# SAOT.net
KiCad netlist of a schematic drawn in EAGLE
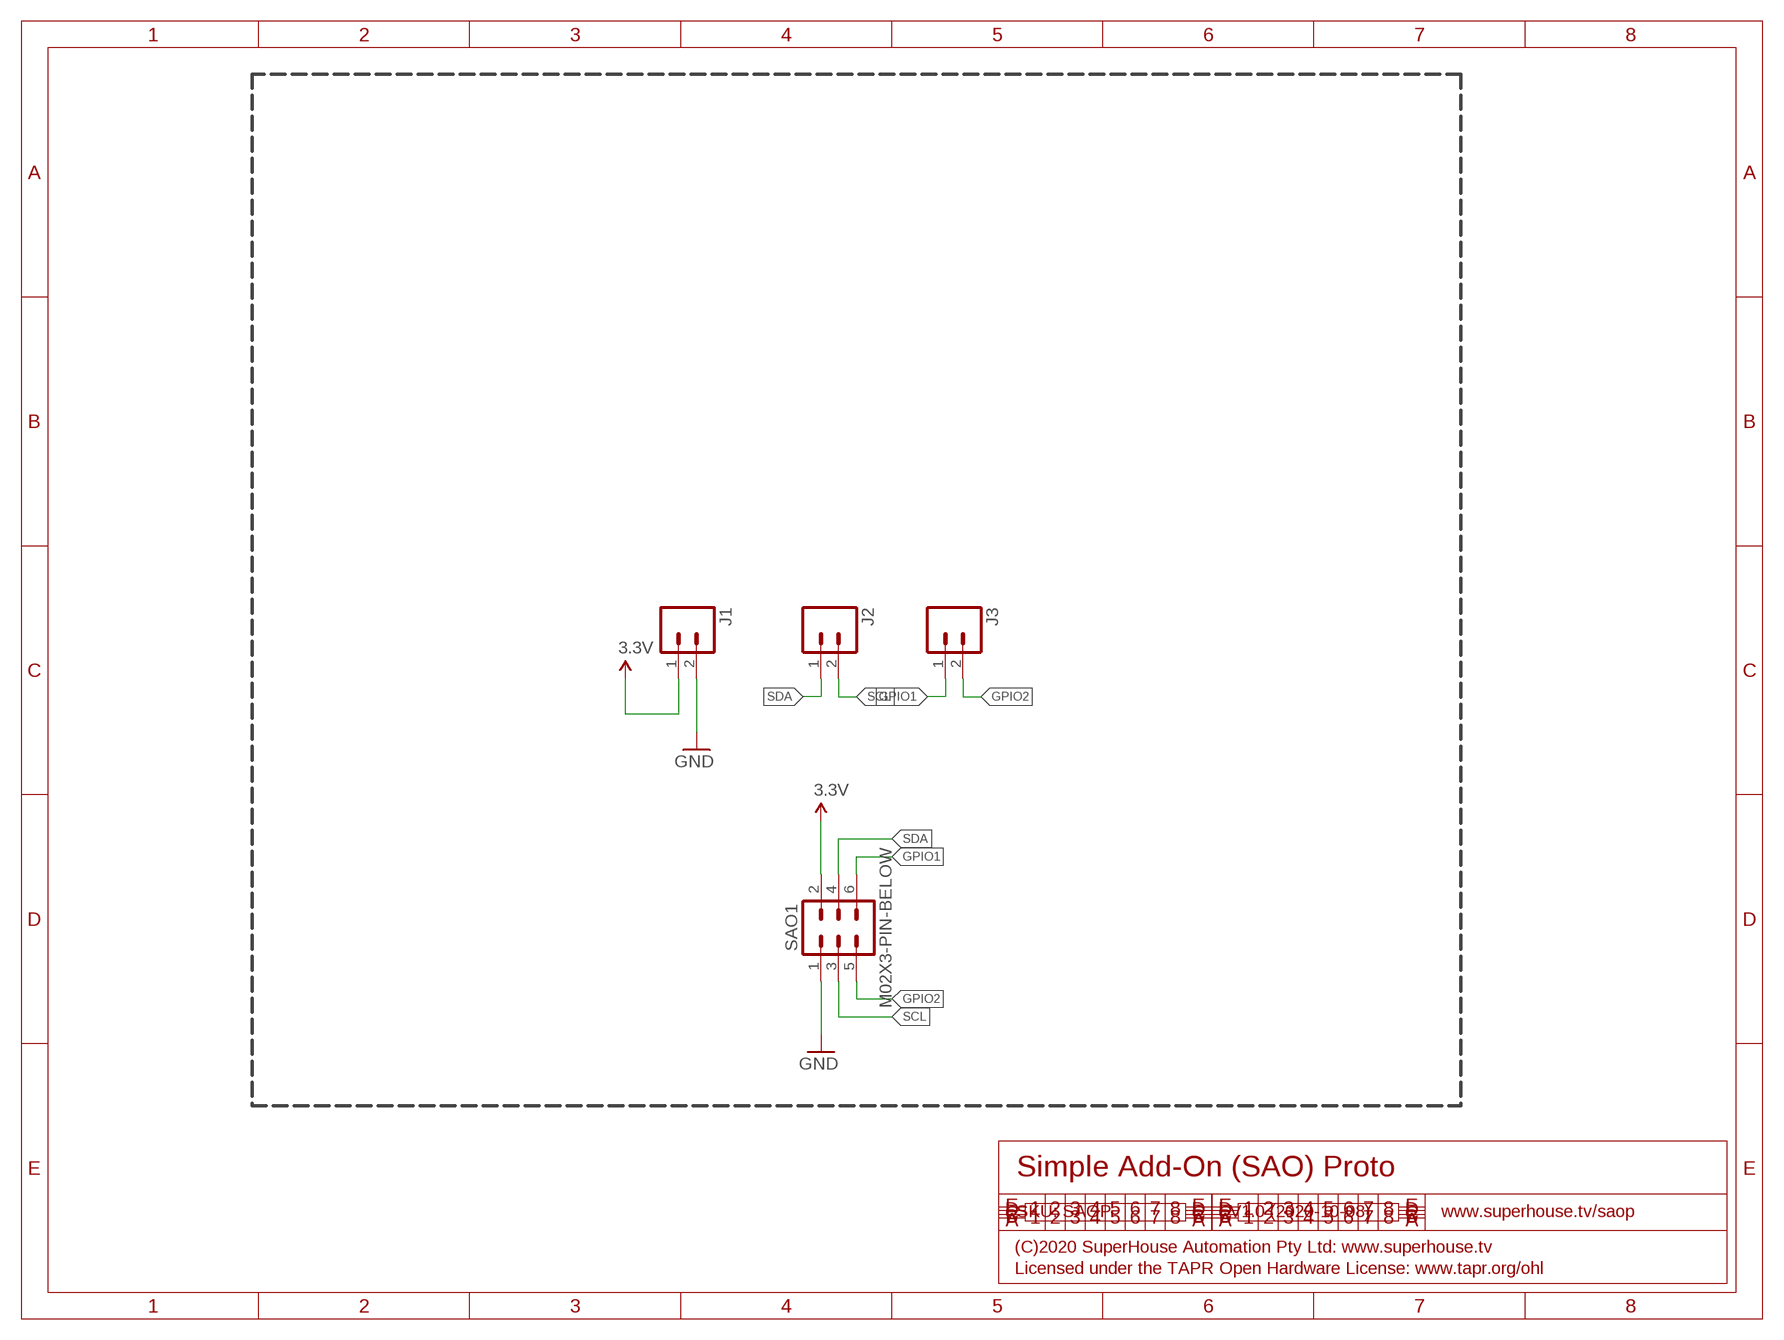
[diagram p0: schematic, sheet 1]

(export (version "E")
  (design (tool "Eeschema 10.0.6"))
  (components
    (comp (ref "J1")
      (value "M02-SCREW-3.5MM")
      (footprint "eagle-import:SCREWTERMINAL-3.5MM-2")
      (libsource (lib "eagle-import") (part "M02-SCREW-3.5MM"))
    )
    (comp (ref "J2")
      (value "M02-SCREW-3.5MM")
      (footprint "eagle-import:SCREWTERMINAL-3.5MM-2")
      (libsource (lib "eagle-import") (part "M02-SCREW-3.5MM"))
    )
    (comp (ref "J3")
      (value "M02-SCREW-3.5MM")
      (footprint "eagle-import:SCREWTERMINAL-3.5MM-2")
      (libsource (lib "eagle-import") (part "M02-SCREW-3.5MM"))
    )
    (comp (ref "SAO1")
      (value "M02X3-PIN-BELOW")
      (footprint "eagle-import:2X03-P-BELOW")
      (libsource (lib "eagle-import") (part "M02X3-PIN-BELOW"))
    )
  )
  (nets
    (net (code "1") (name "3.3V") (class "Default")
      (node (ref "J1") (pin "1") (pinfunction "1_1") (pintype "passive"))
      (node (ref "SAO1") (pin "2") (pinfunction "2_2") (pintype "passive"))
    )
    (net (code "2") (name "GND") (class "Default")
      (node (ref "J1") (pin "2") (pinfunction "2_2") (pintype "passive"))
      (node (ref "SAO1") (pin "1") (pinfunction "1_1") (pintype "passive"))
    )
    (net (code "3") (name "GPIO1") (class "Default")
      (node (ref "J3") (pin "1") (pinfunction "1_1") (pintype "passive"))
      (node (ref "SAO1") (pin "6") (pinfunction "6_6") (pintype "passive"))
    )
    (net (code "4") (name "GPIO2") (class "Default")
      (node (ref "J3") (pin "2") (pinfunction "2_2") (pintype "passive"))
      (node (ref "SAO1") (pin "5") (pinfunction "5_5") (pintype "passive"))
    )
    (net (code "5") (name "SCL") (class "Default")
      (node (ref "J2") (pin "2") (pinfunction "2_2") (pintype "passive"))
      (node (ref "SAO1") (pin "3") (pinfunction "3_3") (pintype "passive"))
    )
    (net (code "6") (name "SDA") (class "Default")
      (node (ref "J2") (pin "1") (pinfunction "1_1") (pintype "passive"))
      (node (ref "SAO1") (pin "4") (pinfunction "4_4") (pintype "passive"))
    )
  )
)
